# isoRS485_block.net
KiCad netlist of a schematic drawn in Altium Designer
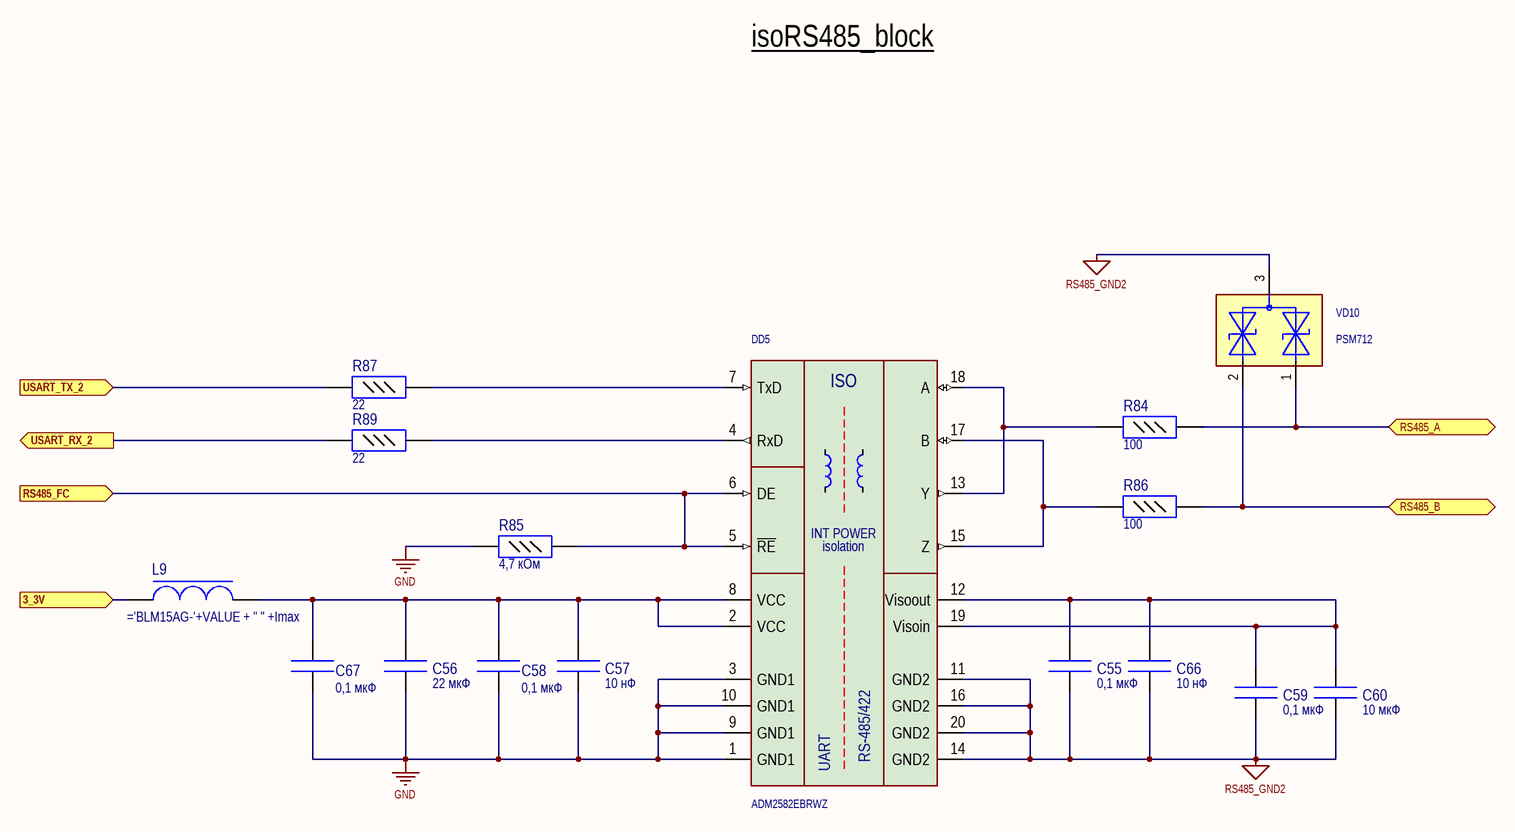
[diagram p0: isoRS485_block.SchDoc]

(export (version "E")
  (design (tool "Eeschema 10.0.6"))
  (components
    (comp (ref "C55")
      (value "0,1 мкФ")
      (footprint "CC0402(1005)")
      (description "Чип конденсатор керамический")
      (fields (field (name "Comment") "CC0402-X7R-0,1 мкФ-20%-50В"))
      (libsource (lib "Конденсаторы") (part "CC0402-X7R-#-20%-50В"))
    )
    (comp (ref "C56")
      (value "22 мкФ")
      (footprint "CC1206")
      (description "Чип конденсатор керамический")
      (fields (field (name "Comment") "CC1206-X7R-22 мкФ-20%-50В"))
      (libsource (lib "Конденсаторы") (part "CC1206-X7R-#-20%-50В"))
    )
    (comp (ref "C57")
      (value "10 нФ")
      (footprint "CC0402(1005)")
      (description "Чип конденсатор керамический")
      (fields (field (name "Comment") "CC0402-X7R-10 нФ-20%-50В"))
      (libsource (lib "Конденсаторы") (part "CC0402-X7R-#-20%-50В"))
    )
    (comp (ref "C58")
      (value "0,1 мкФ")
      (footprint "CC0402(1005)")
      (description "Чип конденсатор керамический")
      (fields (field (name "Comment") "CC0402-X7R-0,1 мкФ-20%-50В"))
      (libsource (lib "Конденсаторы") (part "CC0402-X7R-#-20%-50В"))
    )
    (comp (ref "C59")
      (value "0,1 мкФ")
      (footprint "CC0402(1005)")
      (description "Чип конденсатор керамический")
      (fields (field (name "Comment") "CC0402-X7R-0,1 мкФ-20%-50В"))
      (libsource (lib "Конденсаторы") (part "CC0402-X7R-#-20%-50В"))
    )
    (comp (ref "C60")
      (value "10 мкФ")
      (footprint "CC0603")
      (description "Чип конденсатор керамический")
      (fields (field (name "Comment") "CC0603-X7R-10 мкФ-20%-50В"))
      (libsource (lib "Конденсаторы") (part "CC0603-X7R-#-20%-50В"))
    )
    (comp (ref "C66")
      (value "10 нФ")
      (footprint "CC0402(1005)")
      (description "Чип конденсатор керамический")
      (fields (field (name "Comment") "CC0402-X7R-10 нФ-20%-50В"))
      (libsource (lib "Конденсаторы") (part "CC0402-X7R-#-20%-50В"))
    )
    (comp (ref "C67")
      (value "0,1 мкФ")
      (footprint "CC0402(1005)")
      (description "Чип конденсатор керамический")
      (fields (field (name "Comment") "CC0402-X7R-0,1 мкФ-20%-50В"))
      (libsource (lib "Конденсаторы") (part "CC0402-X7R-#-20%-50В"))
    )
    (comp (ref "DD5")
      (value "ADM2582EBRWZ")
      (footprint "SOIC-W-20")
      (fields (field (name "MANUFACTURER") "Anallog Devices") (field (name "VOLTAGE") "3.3 V or 5 V"))
      (libsource (lib "batmon_ICs") (part "ADM2582E"))
    )
    (comp (ref "L9")
      (value "BLM15AG-600 Ом300 mA")
      (footprint "CL0402(1005)")
      (description "Чип индуктивность подавления EMP")
      (libsource (lib "Индуктивности") (part "BLM15"))
    )
    (comp (ref "R84")
      (value "100")
      (footprint "CR0603")
      (description "Чип резистор")
      (fields (field (name "Comment") "CR0603-100-±5%"))
      (libsource (lib "Резисторы") (part "CR0603-#-±5%"))
    )
    (comp (ref "R85")
      (value "4,7 кОм")
      (footprint "CR0603")
      (description "Чип резистор")
      (fields (field (name "Comment") "CR0603-4,7 кОм-±5%"))
      (libsource (lib "") (part "CR0603-#-±5%_1"))
    )
    (comp (ref "R86")
      (value "100")
      (footprint "CR0603")
      (description "Чип резистор")
      (fields (field (name "Comment") "CR0603-100-±5%"))
      (libsource (lib "Резисторы") (part "CR0603-#-±5%"))
    )
    (comp (ref "R87")
      (value "22")
      (footprint "CR0603")
      (description "Чип резистор")
      (fields (field (name "Comment") "CR0603-22-±5%"))
      (libsource (lib "Резисторы") (part "CR0603-#-±5%"))
    )
    (comp (ref "R89")
      (value "22")
      (footprint "CR0603")
      (description "Чип резистор")
      (fields (field (name "Comment") "CR0603-22-±5%"))
      (libsource (lib "Резисторы") (part "CR0603-#-±5%"))
    )
    (comp (ref "VD10")
      (value "PSM712")
      (footprint "SOT-23")
      (description "ESD RS-485")
      (libsource (lib "Диоды") (part "PSM712"))
    )
  )
  (nets
    (net (code "1") (name "/3_3V") (class "Default")
      (node (ref "L9") (pin "1") (pinfunction "1_1") (pintype "passive"))
    )
    (net (code "2") (name "/RS485_A") (class "Default")
      (node (ref "R84") (pin "2") (pinfunction "-_2") (pintype "passive"))
      (node (ref "VD10") (pin "1") (pintype "passive"))
    )
    (net (code "3") (name "/RS485_B") (class "Default")
      (node (ref "R86") (pin "2") (pinfunction "-_2") (pintype "passive"))
      (node (ref "VD10") (pin "2") (pintype "passive"))
    )
    (net (code "4") (name "/RS485_FC") (class "Default")
      (node (ref "DD5") (pin "5") (pinfunction "~{RE}_5") (pintype "input"))
      (node (ref "DD5") (pin "6") (pinfunction "DE_6") (pintype "input"))
      (node (ref "R85") (pin "1") (pinfunction "+_1") (pintype "passive"))
    )
    (net (code "5") (name "/USART_RX_2") (class "Default")
      (node (ref "R89") (pin "1") (pinfunction "+_1") (pintype "passive"))
    )
    (net (code "6") (name "/USART_TX_2") (class "Default")
      (node (ref "R87") (pin "1") (pinfunction "+_1") (pintype "passive"))
    )
    (net (code "7") (name "GND") (class "Default")
      (node (ref "C56") (pin "2") (pinfunction "-_2") (pintype "passive"))
      (node (ref "C57") (pin "1") (pinfunction "+_1") (pintype "passive"))
      (node (ref "C58") (pin "1") (pinfunction "+_1") (pintype "passive"))
      (node (ref "C67") (pin "1") (pinfunction "+_1") (pintype "passive"))
      (node (ref "DD5") (pin "1") (pinfunction "GND1_1") (pintype "power_in"))
      (node (ref "DD5") (pin "10") (pinfunction "GND1_10") (pintype "power_in"))
      (node (ref "DD5") (pin "3") (pinfunction "GND1_3") (pintype "power_in"))
      (node (ref "DD5") (pin "9") (pinfunction "GND1_9") (pintype "power_in"))
      (node (ref "R85") (pin "2") (pinfunction "-_2") (pintype "passive"))
    )
    (net (code "8") (name "Net-(C55-+)") (class "Default")
      (node (ref "C55") (pin "1") (pinfunction "+_1") (pintype "passive"))
      (node (ref "C59") (pin "1") (pinfunction "+_1") (pintype "passive"))
      (node (ref "C60") (pin "1") (pinfunction "+_1") (pintype "passive"))
      (node (ref "C66") (pin "1") (pinfunction "+_1") (pintype "passive"))
      (node (ref "DD5") (pin "12") (pinfunction "Visoout_12") (pintype "power_in"))
      (node (ref "DD5") (pin "19") (pinfunction "Visoin_19") (pintype "power_in"))
    )
    (net (code "9") (name "Net-(C56-+)") (class "Default")
      (node (ref "C56") (pin "1") (pinfunction "+_1") (pintype "passive"))
      (node (ref "C57") (pin "2") (pinfunction "-_2") (pintype "passive"))
      (node (ref "C58") (pin "2") (pinfunction "-_2") (pintype "passive"))
      (node (ref "C67") (pin "2") (pinfunction "-_2") (pintype "passive"))
      (node (ref "DD5") (pin "2") (pinfunction "VCC_2") (pintype "power_in"))
      (node (ref "DD5") (pin "8") (pinfunction "VCC_8") (pintype "power_in"))
      (node (ref "L9") (pin "2") (pinfunction "2_2") (pintype "passive"))
    )
    (net (code "10") (name "Net-(DD5-A)") (class "Default")
      (node (ref "DD5") (pin "13") (pinfunction "Y_13") (pintype "output"))
      (node (ref "DD5") (pin "18") (pinfunction "A_18") (pintype "bidirectional"))
      (node (ref "R84") (pin "1") (pinfunction "+_1") (pintype "passive"))
    )
    (net (code "11") (name "Net-(DD5-B)") (class "Default")
      (node (ref "DD5") (pin "15") (pinfunction "Z_15") (pintype "output"))
      (node (ref "DD5") (pin "17") (pinfunction "B_17") (pintype "bidirectional"))
      (node (ref "R86") (pin "1") (pinfunction "+_1") (pintype "passive"))
    )
    (net (code "12") (name "Net-(DD5-RxD)") (class "Default")
      (node (ref "DD5") (pin "4") (pinfunction "RxD_4") (pintype "output"))
      (node (ref "R89") (pin "2") (pinfunction "-_2") (pintype "passive"))
    )
    (net (code "13") (name "Net-(DD5-TxD)") (class "Default")
      (node (ref "DD5") (pin "7") (pinfunction "TxD_7") (pintype "input"))
      (node (ref "R87") (pin "2") (pinfunction "-_2") (pintype "passive"))
    )
    (net (code "14") (name "RS485_GND2") (class "Default")
      (node (ref "C55") (pin "2") (pinfunction "-_2") (pintype "passive"))
      (node (ref "C59") (pin "2") (pinfunction "-_2") (pintype "passive"))
      (node (ref "C60") (pin "2") (pinfunction "-_2") (pintype "passive"))
      (node (ref "C66") (pin "2") (pinfunction "-_2") (pintype "passive"))
      (node (ref "DD5") (pin "11") (pinfunction "GND2_11") (pintype "power_in"))
      (node (ref "DD5") (pin "14") (pinfunction "GND2_14") (pintype "power_in"))
      (node (ref "DD5") (pin "16") (pinfunction "GND2_16") (pintype "power_in"))
      (node (ref "DD5") (pin "20") (pinfunction "GND2_20") (pintype "power_in"))
      (node (ref "VD10") (pin "3") (pintype "passive"))
    )
  )
)
